# LedDriverTest1.net
KiCad netlist of a schematic drawn in EAGLE
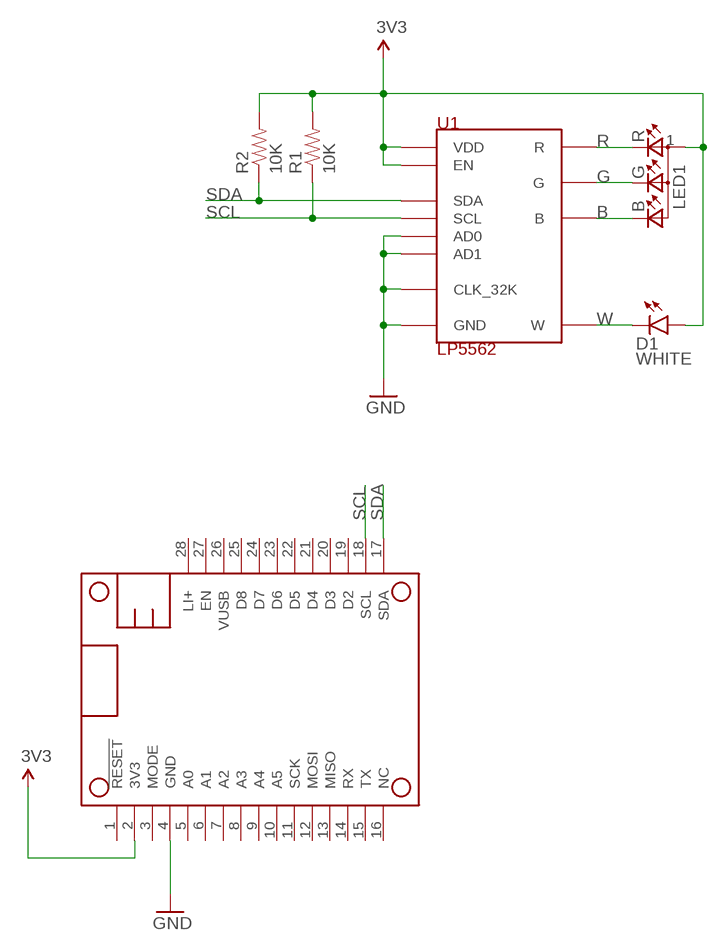
[diagram p0: schematic, sheet 1]

(export (version "E")
  (design (tool "Eeschema 10.0.6"))
  (components
    (comp (ref "D1")
      (value "WHITE")
      (footprint "eagle-import:LED-0603")
      (libsource (lib "eagle-import") (part "LED-WHITE0603"))
    )
    (comp (ref "LED1")
      (value "RGB")
      (footprint "eagle-import:LED-RGB-CREE-SMD")
      (libsource (lib "eagle-import") (part "LED-RGB-CREE-SMD"))
    )
    (comp (ref "MS1")
      (value "FEATHERWING_NODIM")
      (footprint "eagle-import:FEATHERWING_NODIM")
      (libsource (lib "eagle-import") (part "FEATHERWING_NODIM"))
    )
    (comp (ref "R1")
      (value "10K")
      (footprint "eagle-import:0603-RES")
      (libsource (lib "eagle-import") (part "RES-10K-06030603"))
    )
    (comp (ref "R2")
      (value "10K")
      (footprint "eagle-import:0603-RES")
      (libsource (lib "eagle-import") (part "RES-10K-06030603"))
    )
    (comp (ref "U1")
      (value "LP5562")
      (footprint "eagle-import:DSBGA12-TI")
      (libsource (lib "eagle-import") (part "LP5562-LED-DRIVER"))
    )
  )
  (nets
    (net (code "1") (name "/B") (class "Default")
      (node (ref "LED1") (pin "2") (pinfunction "B_2") (pintype "passive"))
      (node (ref "U1") (pin "A4") (pinfunction "B_A4") (pintype "open_collector"))
    )
    (net (code "2") (name "/G") (class "Default")
      (node (ref "LED1") (pin "3") (pinfunction "G_3") (pintype "passive"))
      (node (ref "U1") (pin "B4") (pinfunction "G_B4") (pintype "open_collector"))
    )
    (net (code "3") (name "/LI+") (class "Default")
      (node (ref "MS1") (pin "28") (pinfunction "LI+_28") (pintype "power_in"))
    )
    (net (code "4") (name "/R") (class "Default")
      (node (ref "LED1") (pin "4") (pinfunction "R_4") (pintype "passive"))
      (node (ref "U1") (pin "C4") (pinfunction "R_C4") (pintype "open_collector"))
    )
    (net (code "5") (name "/SCL") (class "Default")
      (node (ref "MS1") (pin "18") (pinfunction "SCL_18") (pintype "bidirectional"))
      (node (ref "R1") (pin "1") (pinfunction "1_1") (pintype "passive"))
      (node (ref "U1") (pin "C2") (pinfunction "SCL_C2") (pintype "input"))
    )
    (net (code "6") (name "/SDA") (class "Default")
      (node (ref "MS1") (pin "17") (pinfunction "SDA_17") (pintype "bidirectional"))
      (node (ref "R2") (pin "1") (pinfunction "1_1") (pintype "passive"))
      (node (ref "U1") (pin "C1") (pinfunction "SDA_C1") (pintype "bidirectional"))
    )
    (net (code "7") (name "/VUSB") (class "Default")
      (node (ref "MS1") (pin "26") (pinfunction "VUSB_26") (pintype "power_in"))
    )
    (net (code "8") (name "/W") (class "Default")
      (node (ref "D1") (pin "C") (pinfunction "C_C") (pintype "passive"))
      (node (ref "U1") (pin "A1") (pinfunction "W_A1") (pintype "open_collector"))
    )
    (net (code "9") (name "3V3") (class "Default")
      (node (ref "D1") (pin "A") (pinfunction "A_A") (pintype "passive"))
      (node (ref "LED1") (pin "1") (pinfunction "A_1") (pintype "passive"))
      (node (ref "MS1") (pin "2") (pinfunction "3V3_2") (pintype "power_in"))
      (node (ref "R1") (pin "2") (pinfunction "2_2") (pintype "passive"))
      (node (ref "R2") (pin "2") (pinfunction "2_2") (pintype "passive"))
      (node (ref "U1") (pin "A2") (pinfunction "VDD_A2") (pintype "power_in"))
      (node (ref "U1") (pin "C3") (pinfunction "EN_C3") (pintype "power_in"))
    )
    (net (code "10") (name "GND") (class "Default")
      (node (ref "MS1") (pin "4") (pinfunction "GND_4") (pintype "power_in"))
      (node (ref "U1") (pin "A3") (pinfunction "CLK_32K_A3") (pintype "input"))
      (node (ref "U1") (pin "B1") (pinfunction "AD1_B1") (pintype "input"))
      (node (ref "U1") (pin "B2") (pinfunction "AD0_B2") (pintype "input"))
      (node (ref "U1") (pin "B3") (pinfunction "GND_B3") (pintype "power_in"))
    )
    (net (code "11") (name "unconnected-(MS1-A0-Pad5)") (class "Default")
      (node (ref "MS1") (pin "5") (pinfunction "A0_5") (pintype "bidirectional"))
    )
    (net (code "12") (name "unconnected-(MS1-A1-Pad6)") (class "Default")
      (node (ref "MS1") (pin "6") (pinfunction "A1_6") (pintype "bidirectional"))
    )
    (net (code "13") (name "unconnected-(MS1-A2-Pad7)") (class "Default")
      (node (ref "MS1") (pin "7") (pinfunction "A2_7") (pintype "bidirectional"))
    )
    (net (code "14") (name "unconnected-(MS1-A3-Pad8)") (class "Default")
      (node (ref "MS1") (pin "8") (pinfunction "A3_8") (pintype "bidirectional"))
    )
    (net (code "15") (name "unconnected-(MS1-A4-Pad9)") (class "Default")
      (node (ref "MS1") (pin "9") (pinfunction "A4_9") (pintype "bidirectional"))
    )
    (net (code "16") (name "unconnected-(MS1-A5-Pad10)") (class "Default")
      (node (ref "MS1") (pin "10") (pinfunction "A5_10") (pintype "bidirectional"))
    )
    (net (code "17") (name "unconnected-(MS1-D2-Pad19)") (class "Default")
      (node (ref "MS1") (pin "19") (pinfunction "D2_19") (pintype "bidirectional"))
    )
    (net (code "18") (name "unconnected-(MS1-D3-Pad20)") (class "Default")
      (node (ref "MS1") (pin "20") (pinfunction "D3_20") (pintype "bidirectional"))
    )
    (net (code "19") (name "unconnected-(MS1-D4-Pad21)") (class "Default")
      (node (ref "MS1") (pin "21") (pinfunction "D4_21") (pintype "bidirectional"))
    )
    (net (code "20") (name "unconnected-(MS1-D5-Pad22)") (class "Default")
      (node (ref "MS1") (pin "22") (pinfunction "D5_22") (pintype "bidirectional"))
    )
    (net (code "21") (name "unconnected-(MS1-D6-Pad23)") (class "Default")
      (node (ref "MS1") (pin "23") (pinfunction "D6_23") (pintype "bidirectional"))
    )
    (net (code "22") (name "unconnected-(MS1-D7-Pad24)") (class "Default")
      (node (ref "MS1") (pin "24") (pinfunction "D7_24") (pintype "bidirectional"))
    )
    (net (code "23") (name "unconnected-(MS1-D8-Pad25)") (class "Default")
      (node (ref "MS1") (pin "25") (pinfunction "D8_25") (pintype "bidirectional"))
    )
    (net (code "24") (name "unconnected-(MS1-EN-Pad27)") (class "Default")
      (node (ref "MS1") (pin "27") (pinfunction "EN_27") (pintype "passive"))
    )
    (net (code "25") (name "unconnected-(MS1-MISO-Pad13)") (class "Default")
      (node (ref "MS1") (pin "13") (pinfunction "MISO_13") (pintype "bidirectional"))
    )
    (net (code "26") (name "unconnected-(MS1-MODE-Pad3)") (class "Default")
      (node (ref "MS1") (pin "3") (pinfunction "MODE_3") (pintype "passive"))
    )
    (net (code "27") (name "unconnected-(MS1-MOSI-Pad12)") (class "Default")
      (node (ref "MS1") (pin "12") (pinfunction "MOSI_12") (pintype "bidirectional"))
    )
    (net (code "28") (name "unconnected-(MS1-NC-Pad16)") (class "Default")
      (node (ref "MS1") (pin "16") (pinfunction "NC_16") (pintype "passive"))
    )
    (net (code "29") (name "unconnected-(MS1-RX-Pad14)") (class "Default")
      (node (ref "MS1") (pin "14") (pinfunction "RX_14") (pintype "bidirectional"))
    )
    (net (code "30") (name "unconnected-(MS1-SCK-Pad11)") (class "Default")
      (node (ref "MS1") (pin "11") (pinfunction "SCK_11") (pintype "bidirectional"))
    )
    (net (code "31") (name "unconnected-(MS1-TX-Pad15)") (class "Default")
      (node (ref "MS1") (pin "15") (pinfunction "TX_15") (pintype "bidirectional"))
    )
    (net (code "32") (name "unconnected-(MS1-~{RESET}-Pad1)") (class "Default")
      (node (ref "MS1") (pin "1") (pinfunction "~{RESET}_1") (pintype "input"))
    )
  )
)
